# kmSigGenTiny_Schematics.net
KiCad netlist of a schematic drawn in EAGLE
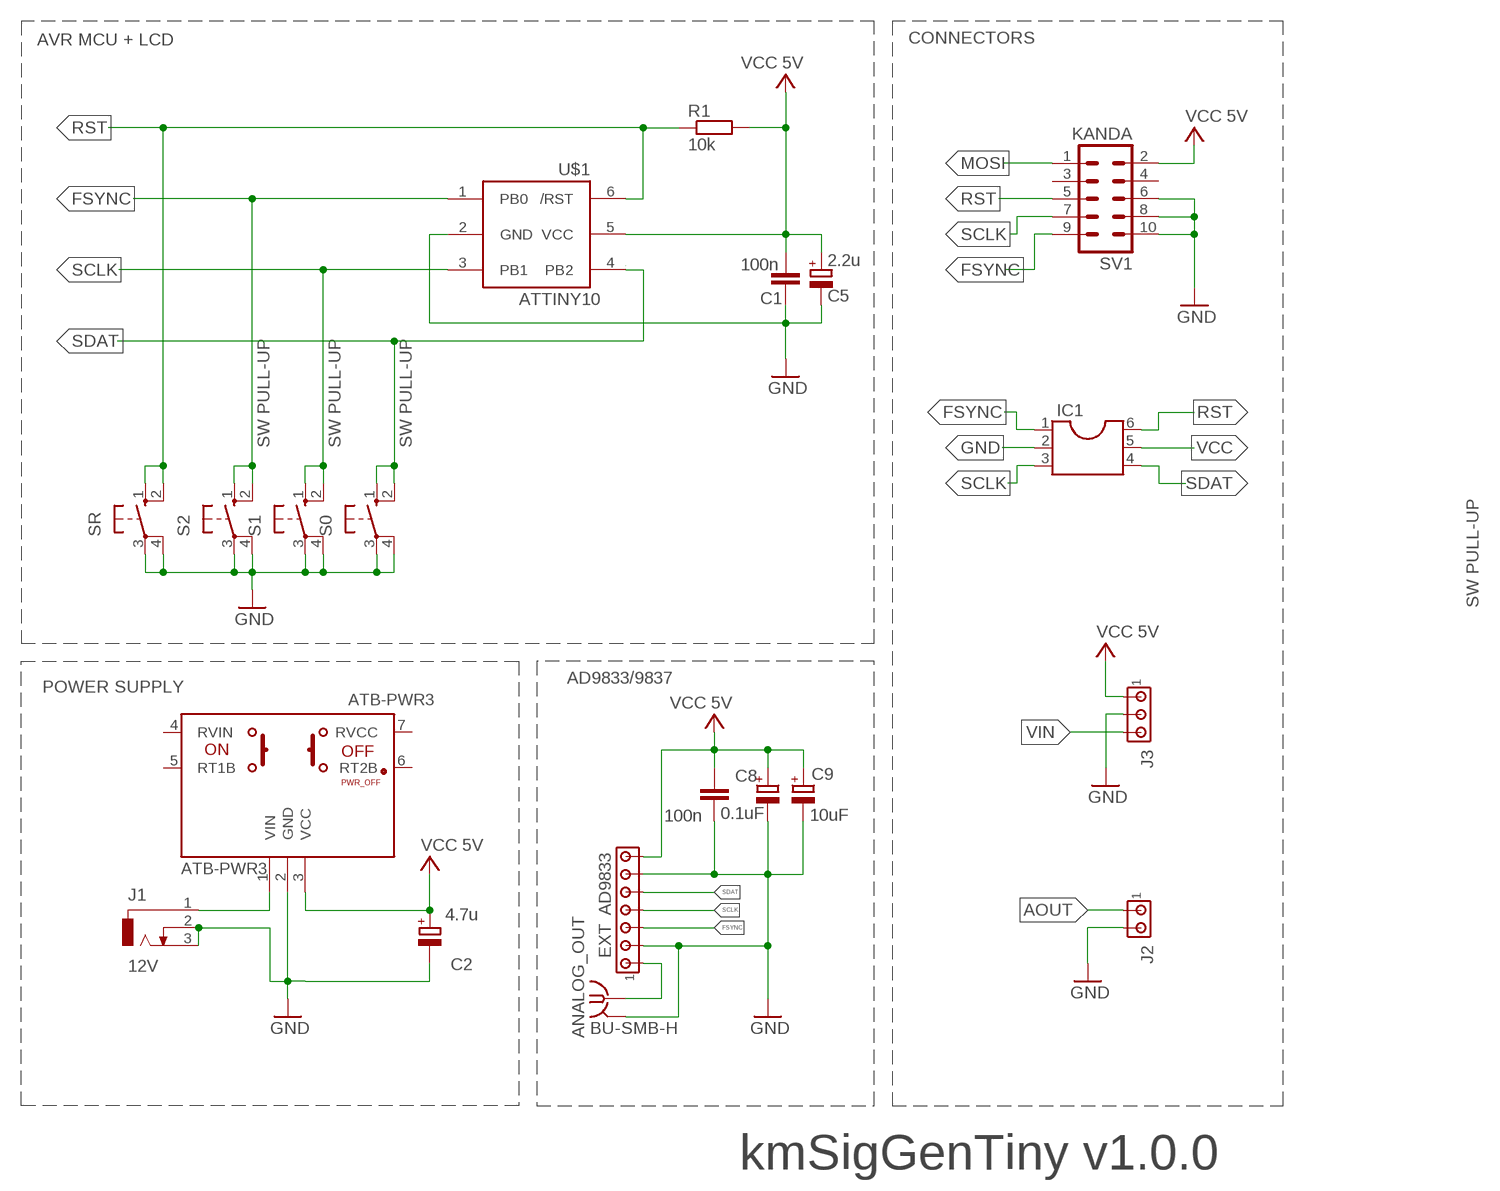
[diagram p0: schematic, sheet 1]

(export (version "E")
  (design (tool "Eeschema 10.0.6"))
  (components
    (comp (ref "ANALOG_OUT")
      (value "BU-SMB-H")
      (footprint "eagle-import:BU-SMB-H")
      (libsource (lib "eagle-import") (part "BU-SMB-H"))
    )
    (comp (ref "ATB-PWR3")
      (value "ATB-PWR3")
      (footprint "eagle-import:ATB-PWR3")
      (libsource (lib "eagle-import") (part "ATB-PWR3"))
    )
    (comp (ref "C1")
      (value "100n")
      (footprint "eagle-import:C2.5-4")
      (libsource (lib "eagle-import") (part "C2.5/4"))
    )
    (comp (ref "C2")
      (value "4.7u")
      (footprint "eagle-import:B45181B")
      (libsource (lib "eagle-import") (part "CPOL-EUB45181B"))
    )
    (comp (ref "C3")
      (value "100n")
      (footprint "eagle-import:C2.5-4")
      (libsource (lib "eagle-import") (part "C2.5/4"))
    )
    (comp (ref "C5")
      (value "2.2u")
      (footprint "eagle-import:B45181B")
      (libsource (lib "eagle-import") (part "CPOL-EUB45181B"))
    )
    (comp (ref "C8")
      (value "0.1uF")
      (footprint "eagle-import:B45181B")
      (libsource (lib "eagle-import") (part "CPOL-EUB45181B"))
    )
    (comp (ref "C9")
      (value "10uF")
      (footprint "eagle-import:B45181B")
      (libsource (lib "eagle-import") (part "CPOL-EUB45181B"))
    )
    (comp (ref "EXT")
      (value "AD9833")
      (footprint "eagle-import:10X07MTA")
      (libsource (lib "eagle-import") (part "MTA07-100"))
    )
    (comp (ref "IC1")
      (value "DIL6")
      (footprint "eagle-import:DIL06")
      (libsource (lib "eagle-import") (part "DIL6"))
    )
    (comp (ref "J1")
      (value "12V")
      (footprint "eagle-import:DCJ0303")
      (libsource (lib "eagle-import") (part "DCJ0303"))
    )
    (comp (ref "J2")
      (value "MTA02-100")
      (footprint "eagle-import:10X02MTA")
      (libsource (lib "eagle-import") (part "MTA02-100"))
    )
    (comp (ref "J3")
      (value "MTA03-100")
      (footprint "eagle-import:10X03MTA")
      (libsource (lib "eagle-import") (part "MTA03-100"))
    )
    (comp (ref "R1")
      (value "10k")
      (footprint "eagle-import:0207_10")
      (libsource (lib "eagle-import") (part "R-EU_0207/10"))
    )
    (comp (ref "S0")
      (value "10-XX")
      (footprint "eagle-import:B3F-10XX")
      (fields (field (name "MPN") "B3F-1000"))
      (libsource (lib "eagle-import") (part "10-XX"))
    )
    (comp (ref "S1")
      (value "10-XX")
      (footprint "eagle-import:B3F-10XX")
      (fields (field (name "MPN") "B3F-1000"))
      (libsource (lib "eagle-import") (part "10-XX"))
    )
    (comp (ref "S2")
      (value "10-XX")
      (footprint "eagle-import:B3F-10XX")
      (fields (field (name "MPN") "B3F-1000"))
      (libsource (lib "eagle-import") (part "10-XX"))
    )
    (comp (ref "SR")
      (value "10-XX")
      (footprint "eagle-import:B3F-10XX")
      (fields (field (name "MPN") "B3F-1000"))
      (libsource (lib "eagle-import") (part "10-XX"))
    )
    (comp (ref "SV1")
      (value "KANDA")
      (footprint "eagle-import:ML10")
      (libsource (lib "eagle-import") (part "ML10"))
    )
    (comp (ref "U$1")
      (value "ATTINY10")
      (footprint "eagle-import:SOT23-6")
      (libsource (lib "eagle-import") (part "ATTINY10"))
    )
  )
  (nets
    (net (code "1") (name "AOUT") (class "Default")
      (node (ref "ANALOG_OUT") (pin "1") (pinfunction "1_1") (pintype "passive"))
      (node (ref "EXT") (pin "1") (pinfunction "1_1") (pintype "passive"))
      (node (ref "J2") (pin "1") (pinfunction "1_1") (pintype "passive"))
    )
    (net (code "2") (name "FSYNC") (class "Default")
      (node (ref "EXT") (pin "3") (pinfunction "3_3") (pintype "passive"))
      (node (ref "IC1") (pin "1") (pinfunction "1_1") (pintype "passive"))
      (node (ref "S2") (pin "1") (pinfunction "S_1") (pintype "passive"))
      (node (ref "S2") (pin "2") (pinfunction "S1_2") (pintype "passive"))
      (node (ref "SV1") (pin "9") (pinfunction "9_9") (pintype "passive"))
      (node (ref "U$1") (pin "1") (pinfunction "PB0_1") (pintype "bidirectional"))
    )
    (net (code "3") (name "GND") (class "Default")
      (node (ref "ANALOG_OUT") (pin "2") (pinfunction "2_2") (pintype "passive"))
      (node (ref "ANALOG_OUT") (pin "3") (pinfunction "2_3") (pintype "passive"))
      (node (ref "ANALOG_OUT") (pin "4") (pinfunction "2_4") (pintype "passive"))
      (node (ref "ANALOG_OUT") (pin "5") (pinfunction "2_5") (pintype "passive"))
      (node (ref "ATB-PWR3") (pin "2") (pinfunction "GND_2") (pintype "power_in"))
      (node (ref "C1") (pin "1") (pinfunction "1_1") (pintype "passive"))
      (node (ref "C2") (pin "-") (pinfunction "-_-") (pintype "passive"))
      (node (ref "C3") (pin "1") (pinfunction "1_1") (pintype "passive"))
      (node (ref "C5") (pin "-") (pinfunction "-_-") (pintype "passive"))
      (node (ref "C8") (pin "-") (pinfunction "-_-") (pintype "passive"))
      (node (ref "C9") (pin "-") (pinfunction "-_-") (pintype "passive"))
      (node (ref "EXT") (pin "2") (pinfunction "2_2") (pintype "passive"))
      (node (ref "EXT") (pin "6") (pinfunction "6_6") (pintype "passive"))
      (node (ref "IC1") (pin "2") (pinfunction "2_2") (pintype "passive"))
      (node (ref "J1") (pin "2") (pinfunction "2_2") (pintype "passive"))
      (node (ref "J1") (pin "3") (pinfunction "3_3") (pintype "passive"))
      (node (ref "J2") (pin "2") (pinfunction "2_2") (pintype "passive"))
      (node (ref "J3") (pin "2") (pinfunction "2_2") (pintype "passive"))
      (node (ref "S0") (pin "3") (pinfunction "P_3") (pintype "passive"))
      (node (ref "S0") (pin "4") (pinfunction "P1_4") (pintype "passive"))
      (node (ref "S1") (pin "3") (pinfunction "P_3") (pintype "passive"))
      (node (ref "S1") (pin "4") (pinfunction "P1_4") (pintype "passive"))
      (node (ref "S2") (pin "3") (pinfunction "P_3") (pintype "passive"))
      (node (ref "S2") (pin "4") (pinfunction "P1_4") (pintype "passive"))
      (node (ref "SR") (pin "3") (pinfunction "P_3") (pintype "passive"))
      (node (ref "SR") (pin "4") (pinfunction "P1_4") (pintype "passive"))
      (node (ref "SV1") (pin "10") (pinfunction "10_10") (pintype "passive"))
      (node (ref "SV1") (pin "6") (pinfunction "6_6") (pintype "passive"))
      (node (ref "SV1") (pin "8") (pinfunction "8_8") (pintype "passive"))
      (node (ref "U$1") (pin "2") (pinfunction "GND_2") (pintype "power_in"))
    )
    (net (code "4") (name "MOSI") (class "Default")
      (node (ref "SV1") (pin "1") (pinfunction "1_1") (pintype "passive"))
    )
    (net (code "5") (name "RST") (class "Default")
      (node (ref "IC1") (pin "6") (pinfunction "6_6") (pintype "passive"))
      (node (ref "R1") (pin "1") (pinfunction "1_1") (pintype "passive"))
      (node (ref "SR") (pin "1") (pinfunction "S_1") (pintype "passive"))
      (node (ref "SR") (pin "2") (pinfunction "S1_2") (pintype "passive"))
      (node (ref "SV1") (pin "5") (pinfunction "5_5") (pintype "passive"))
      (node (ref "U$1") (pin "6") (pinfunction "/RST_6") (pintype "bidirectional"))
    )
    (net (code "6") (name "SCLK") (class "Default")
      (node (ref "EXT") (pin "4") (pinfunction "4_4") (pintype "passive"))
      (node (ref "IC1") (pin "3") (pinfunction "3_3") (pintype "passive"))
      (node (ref "S1") (pin "1") (pinfunction "S_1") (pintype "passive"))
      (node (ref "S1") (pin "2") (pinfunction "S1_2") (pintype "passive"))
      (node (ref "SV1") (pin "7") (pinfunction "7_7") (pintype "passive"))
      (node (ref "U$1") (pin "3") (pinfunction "PB1_3") (pintype "bidirectional"))
    )
    (net (code "7") (name "SDAT") (class "Default")
      (node (ref "EXT") (pin "5") (pinfunction "5_5") (pintype "passive"))
      (node (ref "IC1") (pin "4") (pinfunction "4_4") (pintype "passive"))
      (node (ref "S0") (pin "1") (pinfunction "S_1") (pintype "passive"))
      (node (ref "S0") (pin "2") (pinfunction "S1_2") (pintype "passive"))
      (node (ref "U$1") (pin "4") (pinfunction "PB2_4") (pintype "bidirectional"))
    )
    (net (code "8") (name "VCC") (class "Default")
      (node (ref "ATB-PWR3") (pin "3") (pinfunction "VCC_3") (pintype "power_in"))
      (node (ref "C1") (pin "2") (pinfunction "2_2") (pintype "passive"))
      (node (ref "C2") (pin "+") (pinfunction "+_+") (pintype "passive"))
      (node (ref "C3") (pin "2") (pinfunction "2_2") (pintype "passive"))
      (node (ref "C5") (pin "+") (pinfunction "+_+") (pintype "passive"))
      (node (ref "C8") (pin "+") (pinfunction "+_+") (pintype "passive"))
      (node (ref "C9") (pin "+") (pinfunction "+_+") (pintype "passive"))
      (node (ref "EXT") (pin "7") (pinfunction "7_7") (pintype "passive"))
      (node (ref "IC1") (pin "5") (pinfunction "5_5") (pintype "passive"))
      (node (ref "J3") (pin "1") (pinfunction "1_1") (pintype "passive"))
      (node (ref "R1") (pin "2") (pinfunction "2_2") (pintype "passive"))
      (node (ref "SV1") (pin "2") (pinfunction "2_2") (pintype "passive"))
      (node (ref "U$1") (pin "5") (pinfunction "VCC_5") (pintype "power_in"))
    )
    (net (code "9") (name "VIN") (class "Default")
      (node (ref "ATB-PWR3") (pin "1") (pinfunction "VIN_1") (pintype "power_in"))
      (node (ref "J1") (pin "1") (pinfunction "1_1") (pintype "passive"))
      (node (ref "J3") (pin "3") (pinfunction "3_3") (pintype "passive"))
    )
    (net (code "10") (name "unconnected-(ATB-PWR3-RT1B-Pad5)") (class "Default")
      (node (ref "ATB-PWR3") (pin "5") (pinfunction "RT1B_5") (pintype "input"))
    )
    (net (code "11") (name "unconnected-(ATB-PWR3-RT2B-Pad6)") (class "Default")
      (node (ref "ATB-PWR3") (pin "6") (pinfunction "RT2B_6") (pintype "input"))
    )
    (net (code "12") (name "unconnected-(ATB-PWR3-RVCC-Pad7)") (class "Default")
      (node (ref "ATB-PWR3") (pin "7") (pinfunction "RVCC_7") (pintype "input"))
    )
    (net (code "13") (name "unconnected-(ATB-PWR3-RVIN-Pad4)") (class "Default")
      (node (ref "ATB-PWR3") (pin "4") (pinfunction "RVIN_4") (pintype "input"))
    )
    (net (code "14") (name "unconnected-(SV1-Pad3)") (class "Default")
      (node (ref "SV1") (pin "3") (pinfunction "3_3") (pintype "passive"))
    )
    (net (code "15") (name "unconnected-(SV1-Pad4)") (class "Default")
      (node (ref "SV1") (pin "4") (pinfunction "4_4") (pintype "passive"))
    )
  )
)
